# dhruv.net
KiCad netlist of a schematic drawn in EAGLE
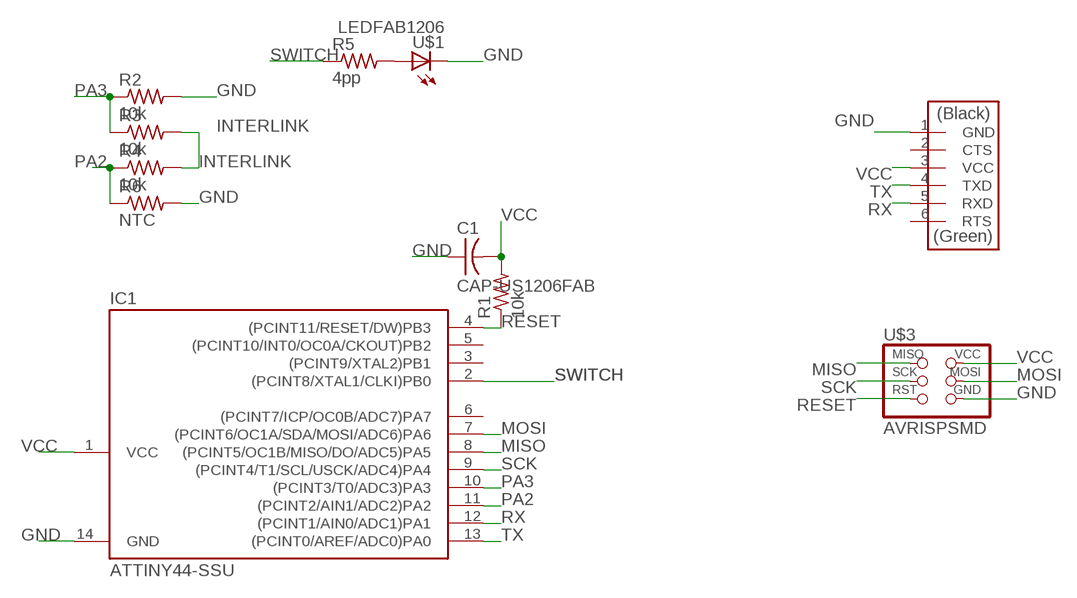
[diagram p0: schematic, sheet 1]

(export (version "E")
  (design (tool "Eeschema 10.0.6"))
  (components
    (comp (ref "C1")
      (value "CAP-US1206FAB")
      (footprint "eagle-import:C1206FAB")
      (libsource (lib "eagle-import") (part "CAP-US1206FAB"))
    )
    (comp (ref "IC1")
      (value "ATTINY44-SSU")
      (footprint "eagle-import:SOIC14")
      (libsource (lib "eagle-import") (part "ATTINY44-SSU"))
    )
    (comp (ref "R1")
      (value "10k")
      (footprint "eagle-import:R1206FAB")
      (libsource (lib "eagle-import") (part "RES-US1206FAB"))
    )
    (comp (ref "R2")
      (value "10k")
      (footprint "eagle-import:R1206FAB")
      (libsource (lib "eagle-import") (part "RES-US1206FAB"))
    )
    (comp (ref "R3")
      (value "10k")
      (footprint "eagle-import:R1206FAB")
      (libsource (lib "eagle-import") (part "RES-US1206FAB"))
    )
    (comp (ref "R4")
      (value "10k")
      (footprint "eagle-import:R1206FAB")
      (libsource (lib "eagle-import") (part "RES-US1206FAB"))
    )
    (comp (ref "R5")
      (value "4pp")
      (footprint "eagle-import:R1206FAB")
      (libsource (lib "eagle-import") (part "RES-US1206FAB"))
    )
    (comp (ref "R6")
      (value "NTC")
      (footprint "eagle-import:R1206FAB")
      (libsource (lib "eagle-import") (part "RES-US1206FAB"))
    )
    (comp (ref "U$1")
      (value "LEDFAB1206")
      (footprint "eagle-import:LED1206FAB")
      (libsource (lib "eagle-import") (part "LEDFAB1206"))
    )
    (comp (ref "U$2")
      (value "FTDI-SMD-HEADER")
      (footprint "eagle-import:1X06SMD")
      (libsource (lib "eagle-import") (part "FTDI-SMD-HEADER"))
    )
    (comp (ref "U$3")
      (value "AVRISPSMD")
      (footprint "eagle-import:2X03SMD")
      (libsource (lib "eagle-import") (part "AVRISPSMD"))
    )
  )
  (nets
    (net (code "1") (name "/GND") (class "Default")
      (node (ref "C1") (pin "1") (pinfunction "1_1") (pintype "passive"))
      (node (ref "IC1") (pin "14") (pinfunction "GND_14") (pintype "power_in"))
      (node (ref "R2") (pin "2") (pinfunction "2_2") (pintype "passive"))
      (node (ref "R6") (pin "2") (pinfunction "2_2") (pintype "passive"))
      (node (ref "U$1") (pin "2") (pinfunction "C_2") (pintype "passive"))
      (node (ref "U$2") (pin "1") (pinfunction "GND_1") (pintype "bidirectional"))
      (node (ref "U$3") (pin "6") (pinfunction "GND_6") (pintype "passive"))
    )
    (net (code "2") (name "/INTERLINK") (class "Default")
      (node (ref "R3") (pin "2") (pinfunction "2_2") (pintype "passive"))
      (node (ref "R4") (pin "2") (pinfunction "2_2") (pintype "passive"))
    )
    (net (code "3") (name "/MISO") (class "Default")
      (node (ref "IC1") (pin "8") (pinfunction "(PCINT5/OC1B/MISO/DO/ADC5)PA5_8") (pintype "bidirectional"))
      (node (ref "U$3") (pin "1") (pinfunction "MISO_1") (pintype "passive"))
    )
    (net (code "4") (name "/MOSI") (class "Default")
      (node (ref "IC1") (pin "7") (pinfunction "(PCINT6/OC1A/SDA/MOSI/ADC6)PA6_7") (pintype "bidirectional"))
      (node (ref "U$3") (pin "4") (pinfunction "MOSI_4") (pintype "passive"))
    )
    (net (code "5") (name "/PA2") (class "Default")
      (node (ref "IC1") (pin "11") (pinfunction "(PCINT2/AIN1/ADC2)PA2_11") (pintype "bidirectional"))
      (node (ref "R4") (pin "1") (pinfunction "1_1") (pintype "passive"))
      (node (ref "R6") (pin "1") (pinfunction "1_1") (pintype "passive"))
    )
    (net (code "6") (name "/PA3") (class "Default")
      (node (ref "IC1") (pin "10") (pinfunction "(PCINT3/T0/ADC3)PA3_10") (pintype "bidirectional"))
      (node (ref "R2") (pin "1") (pinfunction "1_1") (pintype "passive"))
      (node (ref "R3") (pin "1") (pinfunction "1_1") (pintype "passive"))
    )
    (net (code "7") (name "/RESET") (class "Default")
      (node (ref "IC1") (pin "4") (pinfunction "(PCINT11/RESET/DW)PB3_4") (pintype "bidirectional"))
      (node (ref "R1") (pin "1") (pinfunction "1_1") (pintype "passive"))
      (node (ref "U$3") (pin "5") (pinfunction "RST_5") (pintype "passive"))
    )
    (net (code "8") (name "/RX") (class "Default")
      (node (ref "IC1") (pin "12") (pinfunction "(PCINT1/AIN0/ADC1)PA1_12") (pintype "bidirectional"))
      (node (ref "U$2") (pin "5") (pinfunction "RXD_5") (pintype "bidirectional"))
    )
    (net (code "9") (name "/SCK") (class "Default")
      (node (ref "IC1") (pin "9") (pinfunction "(PCINT4/T1/SCL/USCK/ADC4)PA4_9") (pintype "bidirectional"))
      (node (ref "U$3") (pin "3") (pinfunction "SCK_3") (pintype "passive"))
    )
    (net (code "10") (name "/SWITCH") (class "Default")
      (node (ref "IC1") (pin "2") (pinfunction "(PCINT8/XTAL1/CLKI)PB0_2") (pintype "bidirectional"))
      (node (ref "R5") (pin "1") (pinfunction "1_1") (pintype "passive"))
    )
    (net (code "11") (name "/TX") (class "Default")
      (node (ref "IC1") (pin "13") (pinfunction "(PCINT0/AREF/ADC0)PA0_13") (pintype "bidirectional"))
      (node (ref "U$2") (pin "4") (pinfunction "TXD_4") (pintype "bidirectional"))
    )
    (net (code "12") (name "/VCC") (class "Default")
      (node (ref "C1") (pin "2") (pinfunction "2_2") (pintype "passive"))
      (node (ref "IC1") (pin "1") (pinfunction "VCC_1") (pintype "power_in"))
      (node (ref "R1") (pin "2") (pinfunction "2_2") (pintype "passive"))
      (node (ref "U$2") (pin "3") (pinfunction "VCC_3") (pintype "bidirectional"))
      (node (ref "U$3") (pin "2") (pinfunction "VCC_2") (pintype "passive"))
    )
    (net (code "13") (name "Net-(U$1-A)") (class "Default")
      (node (ref "R5") (pin "2") (pinfunction "2_2") (pintype "passive"))
      (node (ref "U$1") (pin "1") (pinfunction "A_1") (pintype "passive"))
    )
    (net (code "14") (name "unconnected-(IC1-(PCINT7{slash}ICP{slash}OC0B{slash}ADC7)PA7-Pad6)") (class "Default")
      (node (ref "IC1") (pin "6") (pinfunction "(PCINT7/ICP/OC0B/ADC7)PA7_6") (pintype "bidirectional"))
    )
    (net (code "15") (name "unconnected-(IC1-(PCINT9{slash}XTAL2)PB1-Pad3)") (class "Default")
      (node (ref "IC1") (pin "3") (pinfunction "(PCINT9/XTAL2)PB1_3") (pintype "bidirectional"))
    )
    (net (code "16") (name "unconnected-(IC1-(PCINT10{slash}INT0{slash}OC0A{slash}CKOUT)PB2-Pad5)") (class "Default")
      (node (ref "IC1") (pin "5") (pinfunction "(PCINT10/INT0/OC0A/CKOUT)PB2_5") (pintype "bidirectional"))
    )
    (net (code "17") (name "unconnected-(U$2-CTS-Pad2)") (class "Default")
      (node (ref "U$2") (pin "2") (pinfunction "CTS_2") (pintype "bidirectional"))
    )
    (net (code "18") (name "unconnected-(U$2-RTS-Pad6)") (class "Default")
      (node (ref "U$2") (pin "6") (pinfunction "RTS_6") (pintype "bidirectional"))
    )
  )
)
